# LP2985_1v8.net
KiCad netlist of a schematic drawn in EAGLE
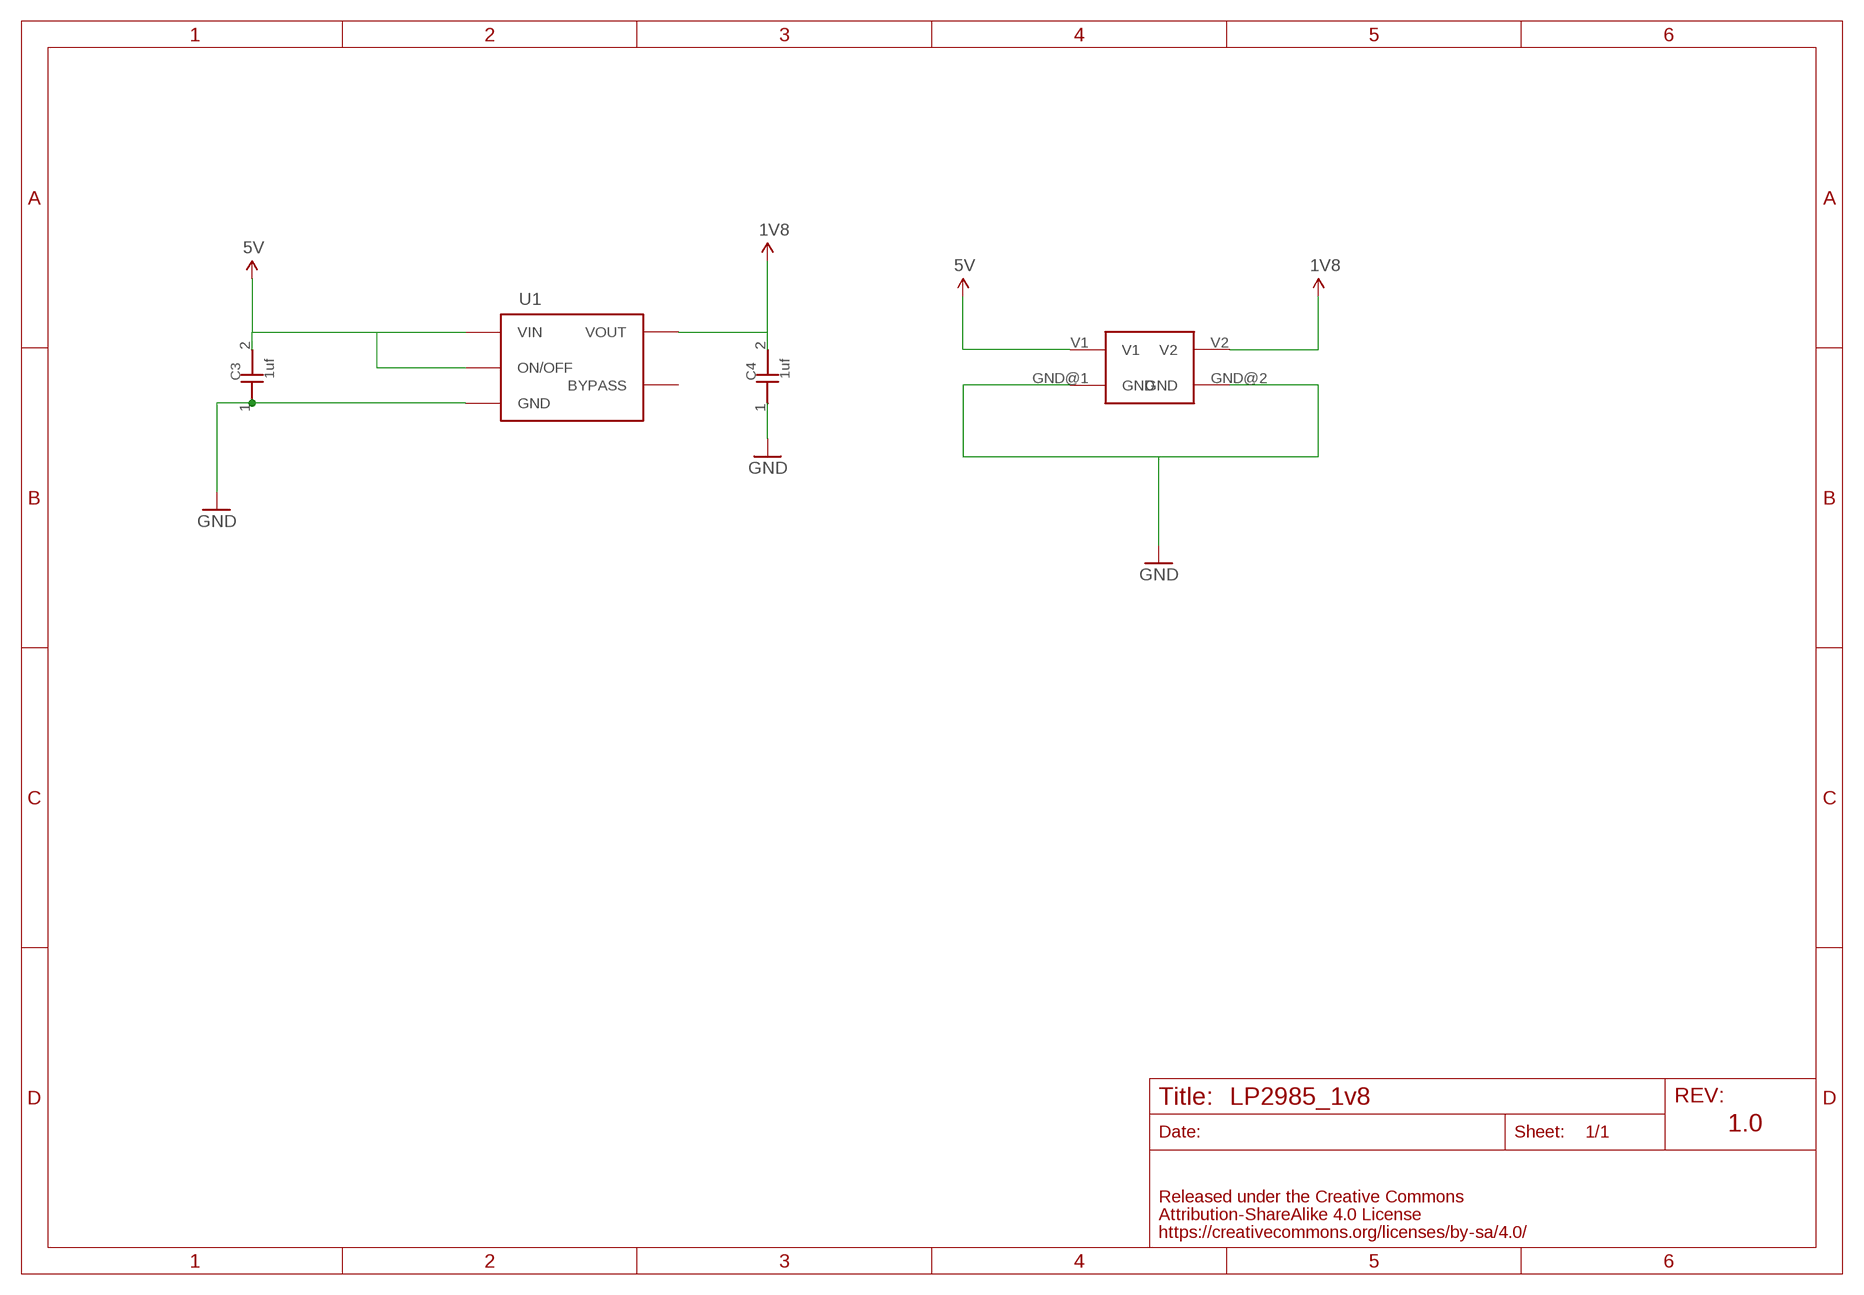
[diagram p0: schematic, sheet 1]

(export (version "E")
  (design (tool "Eeschema 10.0.6"))
  (components
    (comp (ref "C3")
      (value "1uf")
      (footprint "eagle-import:0603")
      (libsource (lib "eagle-import") (part "CAPACITOR0603"))
    )
    (comp (ref "C4")
      (value "1uf")
      (footprint "eagle-import:0603")
      (libsource (lib "eagle-import") (part "CAPACITOR0603"))
    )
    (comp (ref "U$2")
      (value "4PIN-REGULATOR")
      (footprint "eagle-import:4PIN-REGULATOR")
      (libsource (lib "eagle-import") (part "4PIN-REGULATOR"))
    )
    (comp (ref "U1")
      (value "LP2985-33DBVR")
      (footprint "eagle-import:SOT_23_5")
      (libsource (lib "eagle-import") (part "LP2985-33DBVR"))
    )
  )
  (nets
    (net (code "1") (name "1V8") (class "Default")
      (node (ref "C4") (pin "2") (pinfunction "2_2") (pintype "passive"))
      (node (ref "U$2") (pin "V2") (pinfunction "V2_V2") (pintype "bidirectional"))
      (node (ref "U1") (pin "5") (pinfunction "VOUT_5") (pintype "output"))
    )
    (net (code "2") (name "5V") (class "Default")
      (node (ref "C3") (pin "2") (pinfunction "2_2") (pintype "passive"))
      (node (ref "U$2") (pin "V1") (pinfunction "V1_V1") (pintype "bidirectional"))
      (node (ref "U1") (pin "1") (pinfunction "VIN_1") (pintype "input"))
      (node (ref "U1") (pin "3") (pinfunction "ON/OFF_3") (pintype "input"))
    )
    (net (code "3") (name "GND") (class "Default")
      (node (ref "C3") (pin "1") (pinfunction "1_1") (pintype "passive"))
      (node (ref "C4") (pin "1") (pinfunction "1_1") (pintype "passive"))
      (node (ref "U$2") (pin "GND@1") (pinfunction "GND_GND@1") (pintype "bidirectional"))
      (node (ref "U$2") (pin "GND@2") (pinfunction "GND_GND@2") (pintype "bidirectional"))
      (node (ref "U1") (pin "2") (pinfunction "GND_2") (pintype "power_in"))
    )
    (net (code "4") (name "unconnected-(U1-BYPASS-Pad4)") (class "Default")
      (node (ref "U1") (pin "4") (pinfunction "BYPASS_4") (pintype "bidirectional"))
    )
  )
)
